# LCD.net
KiCad netlist of a schematic drawn in Altium Designer
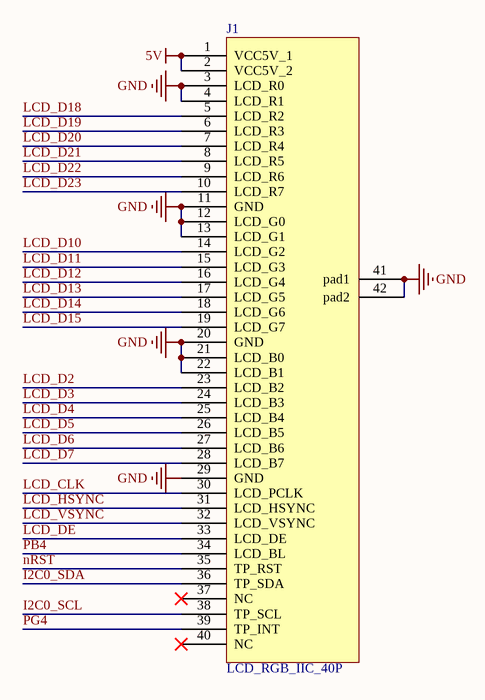
[diagram p0: LCD.SchDoc]

(export (version "E")
  (design (tool "Eeschema 10.0.6"))
  (components
    (comp (ref "J1")
      (value "LCD_RGB_IIC_40P")
      (footprint "FPC_40P")
      (description "自制LCD接口,RGB+IIC触摸，40P")
      (libsource (lib "momo") (part "LCD_RGB_IIC_40P"))
    )
  )
  (nets
    (net (code "1") (name "/I2C0_SCL") (class "Default")
      (node (ref "J1") (pin "38") (pinfunction "TP_SCL_38") (pintype "passive"))
    )
    (net (code "2") (name "/I2C0_SDA") (class "Default")
      (node (ref "J1") (pin "36") (pinfunction "TP_SDA_36") (pintype "passive"))
    )
    (net (code "3") (name "/LCD_CLK") (class "Default")
      (node (ref "J1") (pin "30") (pinfunction "LCD_PCLK_30") (pintype "passive"))
    )
    (net (code "4") (name "/LCD_D2") (class "Default")
      (node (ref "J1") (pin "23") (pinfunction "LCD_B2_23") (pintype "power_in"))
    )
    (net (code "5") (name "/LCD_D3") (class "Default")
      (node (ref "J1") (pin "24") (pinfunction "LCD_B3_24") (pintype "power_in"))
    )
    (net (code "6") (name "/LCD_D4") (class "Default")
      (node (ref "J1") (pin "25") (pinfunction "LCD_B4_25") (pintype "power_in"))
    )
    (net (code "7") (name "/LCD_D5") (class "Default")
      (node (ref "J1") (pin "26") (pinfunction "LCD_B5_26") (pintype "power_in"))
    )
    (net (code "8") (name "/LCD_D6") (class "Default")
      (node (ref "J1") (pin "27") (pinfunction "LCD_B6_27") (pintype "power_in"))
    )
    (net (code "9") (name "/LCD_D7") (class "Default")
      (node (ref "J1") (pin "28") (pinfunction "LCD_B7_28") (pintype "power_in"))
    )
    (net (code "10") (name "/LCD_D10") (class "Default")
      (node (ref "J1") (pin "14") (pinfunction "LCD_G2_14") (pintype "power_in"))
    )
    (net (code "11") (name "/LCD_D11") (class "Default")
      (node (ref "J1") (pin "15") (pinfunction "LCD_G3_15") (pintype "power_in"))
    )
    (net (code "12") (name "/LCD_D12") (class "Default")
      (node (ref "J1") (pin "16") (pinfunction "LCD_G4_16") (pintype "power_in"))
    )
    (net (code "13") (name "/LCD_D13") (class "Default")
      (node (ref "J1") (pin "17") (pinfunction "LCD_G5_17") (pintype "power_in"))
    )
    (net (code "14") (name "/LCD_D14") (class "Default")
      (node (ref "J1") (pin "18") (pinfunction "LCD_G6_18") (pintype "power_in"))
    )
    (net (code "15") (name "/LCD_D15") (class "Default")
      (node (ref "J1") (pin "19") (pinfunction "LCD_G7_19") (pintype "power_in"))
    )
    (net (code "16") (name "/LCD_D18") (class "Default")
      (node (ref "J1") (pin "5") (pinfunction "LCD_R2_5") (pintype "power_in"))
    )
    (net (code "17") (name "/LCD_D19") (class "Default")
      (node (ref "J1") (pin "6") (pinfunction "LCD_R3_6") (pintype "power_in"))
    )
    (net (code "18") (name "/LCD_D20") (class "Default")
      (node (ref "J1") (pin "7") (pinfunction "LCD_R4_7") (pintype "power_in"))
    )
    (net (code "19") (name "/LCD_D21") (class "Default")
      (node (ref "J1") (pin "8") (pinfunction "LCD_R5_8") (pintype "power_in"))
    )
    (net (code "20") (name "/LCD_D22") (class "Default")
      (node (ref "J1") (pin "9") (pinfunction "LCD_R6_9") (pintype "power_in"))
    )
    (net (code "21") (name "/LCD_D23") (class "Default")
      (node (ref "J1") (pin "10") (pinfunction "LCD_R7_10") (pintype "power_in"))
    )
    (net (code "22") (name "/LCD_DE") (class "Default")
      (node (ref "J1") (pin "33") (pinfunction "LCD_DE_33") (pintype "passive"))
    )
    (net (code "23") (name "/LCD_HSYNC") (class "Default")
      (node (ref "J1") (pin "31") (pinfunction "LCD_HSYNC_31") (pintype "passive"))
    )
    (net (code "24") (name "/LCD_VSYNC") (class "Default")
      (node (ref "J1") (pin "32") (pinfunction "LCD_VSYNC_32") (pintype "passive"))
    )
    (net (code "25") (name "/PB4") (class "Default")
      (node (ref "J1") (pin "34") (pinfunction "LCD_BL_34") (pintype "passive"))
    )
    (net (code "26") (name "/PG4") (class "Default")
      (node (ref "J1") (pin "39") (pinfunction "TP_INT_39") (pintype "passive"))
    )
    (net (code "27") (name "/nRST") (class "Default")
      (node (ref "J1") (pin "35") (pinfunction "TP_RST_35") (pintype "passive"))
    )
    (net (code "28") (name "5V") (class "Default")
      (node (ref "J1") (pin "1") (pinfunction "VCC5V_1_1") (pintype "passive"))
      (node (ref "J1") (pin "2") (pinfunction "VCC5V_2_2") (pintype "passive"))
    )
    (net (code "29") (name "GND") (class "Default")
      (node (ref "J1") (pin "11") (pinfunction "GND_11") (pintype "power_in"))
      (node (ref "J1") (pin "12") (pinfunction "LCD_G0_12") (pintype "power_in"))
      (node (ref "J1") (pin "13") (pinfunction "LCD_G1_13") (pintype "power_in"))
      (node (ref "J1") (pin "20") (pinfunction "GND_20") (pintype "power_in"))
      (node (ref "J1") (pin "21") (pinfunction "LCD_B0_21") (pintype "power_in"))
      (node (ref "J1") (pin "22") (pinfunction "LCD_B1_22") (pintype "power_in"))
      (node (ref "J1") (pin "29") (pinfunction "GND_29") (pintype "power_in"))
      (node (ref "J1") (pin "3") (pinfunction "LCD_R0_3") (pintype "passive"))
      (node (ref "J1") (pin "4") (pinfunction "LCD_R1_4") (pintype "passive"))
      (node (ref "J1") (pin "41") (pinfunction "pad1_41") (pintype "power_in"))
      (node (ref "J1") (pin "42") (pinfunction "pad2_42") (pintype "power_in"))
    )
    (net (code "30") (name "unconnected-(J1-NC-Pad37)") (class "Default")
      (node (ref "J1") (pin "37") (pinfunction "NC_37") (pintype "power_in+no_connect"))
    )
    (net (code "31") (name "unconnected-(J1-NC-Pad40)") (class "Default")
      (node (ref "J1") (pin "40") (pinfunction "NC_40") (pintype "power_in+no_connect"))
    )
  )
)
